# hbridge.net
KiCad netlist of a schematic drawn in EAGLE
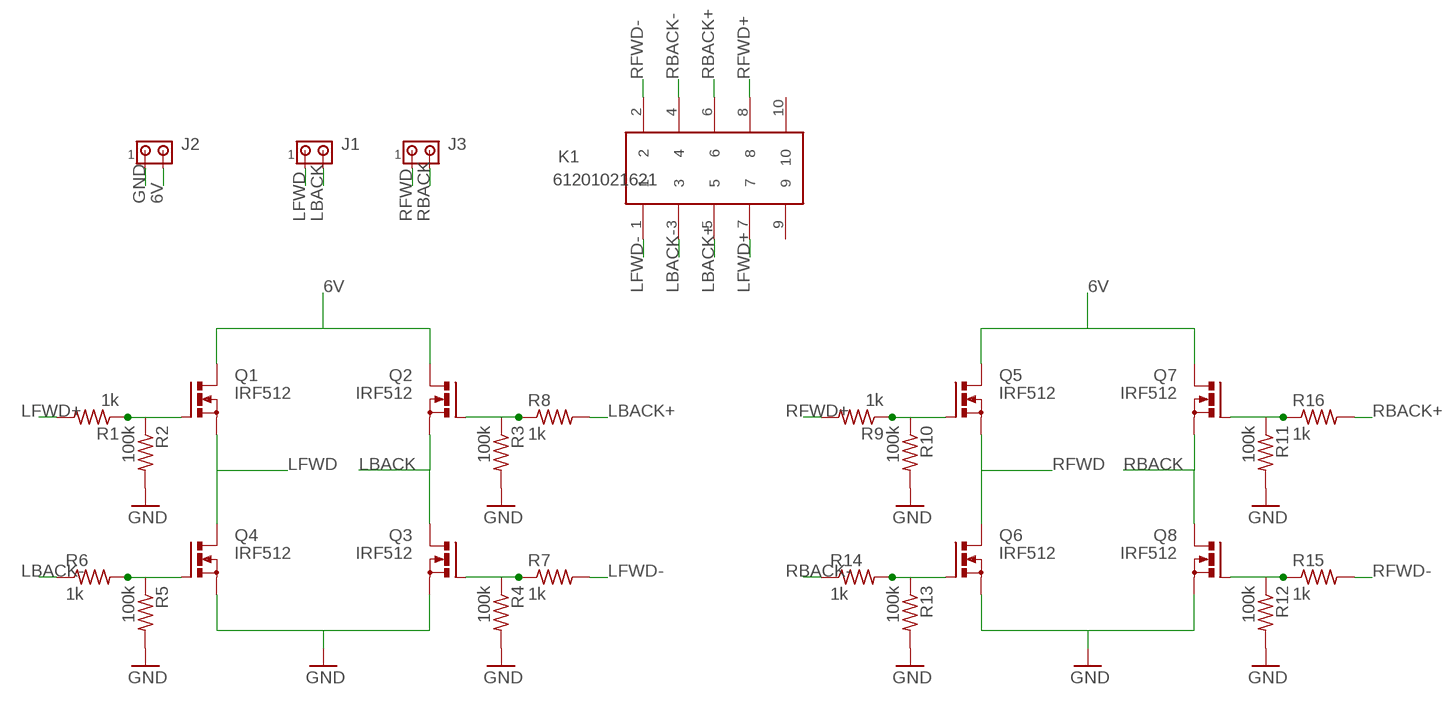
[diagram p0: schematic, sheet 1]

(export (version "E")
  (design (tool "Eeschema 10.0.6"))
  (components
    (comp (ref "J1")
      (value "MTA02-100")
      (footprint "eagle-import:10X02MTA")
      (libsource (lib "eagle-import") (part "MTA02-100"))
    )
    (comp (ref "J2")
      (value "MTA02-100")
      (footprint "eagle-import:10X02MTA")
      (libsource (lib "eagle-import") (part "MTA02-100"))
    )
    (comp (ref "J3")
      (value "MTA02-100")
      (footprint "eagle-import:10X02MTA")
      (libsource (lib "eagle-import") (part "MTA02-100"))
    )
    (comp (ref "K1")
      (value "61201021621")
      (footprint "eagle-import:61201021621")
      (libsource (lib "eagle-import") (part "61201021621"))
    )
    (comp (ref "Q1")
      (value "IRF512")
      (footprint "eagle-import:TO220BV")
      (libsource (lib "eagle-import") (part "IRF512"))
    )
    (comp (ref "Q2")
      (value "IRF512")
      (footprint "eagle-import:TO220BV")
      (libsource (lib "eagle-import") (part "IRF512"))
    )
    (comp (ref "Q3")
      (value "IRF512")
      (footprint "eagle-import:TO220BV")
      (libsource (lib "eagle-import") (part "IRF512"))
    )
    (comp (ref "Q4")
      (value "IRF512")
      (footprint "eagle-import:TO220BV")
      (libsource (lib "eagle-import") (part "IRF512"))
    )
    (comp (ref "Q5")
      (value "IRF512")
      (footprint "eagle-import:TO220BV")
      (libsource (lib "eagle-import") (part "IRF512"))
    )
    (comp (ref "Q6")
      (value "IRF512")
      (footprint "eagle-import:TO220BV")
      (libsource (lib "eagle-import") (part "IRF512"))
    )
    (comp (ref "Q7")
      (value "IRF512")
      (footprint "eagle-import:TO220BV")
      (libsource (lib "eagle-import") (part "IRF512"))
    )
    (comp (ref "Q8")
      (value "IRF512")
      (footprint "eagle-import:TO220BV")
      (libsource (lib "eagle-import") (part "IRF512"))
    )
    (comp (ref "R1")
      (value "1k")
      (footprint "eagle-import:0204_7")
      (libsource (lib "eagle-import") (part "R-US_0204/7"))
    )
    (comp (ref "R2")
      (value "100k")
      (footprint "eagle-import:0204_7")
      (libsource (lib "eagle-import") (part "R-US_0204/7"))
    )
    (comp (ref "R3")
      (value "100k")
      (footprint "eagle-import:0204_7")
      (libsource (lib "eagle-import") (part "R-US_0204/7"))
    )
    (comp (ref "R4")
      (value "100k")
      (footprint "eagle-import:0204_7")
      (libsource (lib "eagle-import") (part "R-US_0204/7"))
    )
    (comp (ref "R5")
      (value "100k")
      (footprint "eagle-import:0204_7")
      (libsource (lib "eagle-import") (part "R-US_0204/7"))
    )
    (comp (ref "R6")
      (value "1k")
      (footprint "eagle-import:0204_7")
      (libsource (lib "eagle-import") (part "R-US_0204/7"))
    )
    (comp (ref "R7")
      (value "1k")
      (footprint "eagle-import:0204_7")
      (libsource (lib "eagle-import") (part "R-US_0204/7"))
    )
    (comp (ref "R8")
      (value "1k")
      (footprint "eagle-import:0204_7")
      (libsource (lib "eagle-import") (part "R-US_0204/7"))
    )
    (comp (ref "R9")
      (value "1k")
      (footprint "eagle-import:0204_7")
      (libsource (lib "eagle-import") (part "R-US_0204/7"))
    )
    (comp (ref "R10")
      (value "100k")
      (footprint "eagle-import:0204_7")
      (libsource (lib "eagle-import") (part "R-US_0204/7"))
    )
    (comp (ref "R11")
      (value "100k")
      (footprint "eagle-import:0204_7")
      (libsource (lib "eagle-import") (part "R-US_0204/7"))
    )
    (comp (ref "R12")
      (value "100k")
      (footprint "eagle-import:0204_7")
      (libsource (lib "eagle-import") (part "R-US_0204/7"))
    )
    (comp (ref "R13")
      (value "100k")
      (footprint "eagle-import:0204_7")
      (libsource (lib "eagle-import") (part "R-US_0204/7"))
    )
    (comp (ref "R14")
      (value "1k")
      (footprint "eagle-import:0204_7")
      (libsource (lib "eagle-import") (part "R-US_0204/7"))
    )
    (comp (ref "R15")
      (value "1k")
      (footprint "eagle-import:0204_7")
      (libsource (lib "eagle-import") (part "R-US_0204/7"))
    )
    (comp (ref "R16")
      (value "1k")
      (footprint "eagle-import:0204_7")
      (libsource (lib "eagle-import") (part "R-US_0204/7"))
    )
  )
  (nets
    (net (code "1") (name "/6V") (class "Default")
      (node (ref "J2") (pin "2") (pinfunction "2_2") (pintype "passive"))
      (node (ref "Q1") (pin "D") (pinfunction "D_D") (pintype "passive"))
      (node (ref "Q2") (pin "D") (pinfunction "D_D") (pintype "passive"))
      (node (ref "Q5") (pin "D") (pinfunction "D_D") (pintype "passive"))
      (node (ref "Q7") (pin "D") (pinfunction "D_D") (pintype "passive"))
    )
    (net (code "2") (name "/LBACK") (class "Default")
      (node (ref "J1") (pin "2") (pinfunction "2_2") (pintype "passive"))
      (node (ref "Q2") (pin "S") (pinfunction "S_S") (pintype "passive"))
      (node (ref "Q3") (pin "D") (pinfunction "D_D") (pintype "passive"))
    )
    (net (code "3") (name "/LBACK+") (class "Default")
      (node (ref "K1") (pin "5") (pinfunction "5_5") (pintype "passive"))
      (node (ref "R8") (pin "2") (pinfunction "2_2") (pintype "passive"))
    )
    (net (code "4") (name "/LBACK-") (class "Default")
      (node (ref "K1") (pin "3") (pinfunction "3_3") (pintype "passive"))
      (node (ref "R6") (pin "1") (pinfunction "1_1") (pintype "passive"))
    )
    (net (code "5") (name "/LFWD") (class "Default")
      (node (ref "J1") (pin "1") (pinfunction "1_1") (pintype "passive"))
      (node (ref "Q1") (pin "S") (pinfunction "S_S") (pintype "passive"))
      (node (ref "Q4") (pin "D") (pinfunction "D_D") (pintype "passive"))
    )
    (net (code "6") (name "/LFWD+") (class "Default")
      (node (ref "K1") (pin "7") (pinfunction "7_7") (pintype "passive"))
      (node (ref "R1") (pin "2") (pinfunction "2_2") (pintype "passive"))
    )
    (net (code "7") (name "/LFWD-") (class "Default")
      (node (ref "K1") (pin "1") (pinfunction "1_1") (pintype "passive"))
      (node (ref "R7") (pin "2") (pinfunction "2_2") (pintype "passive"))
    )
    (net (code "8") (name "/RBACK") (class "Default")
      (node (ref "J3") (pin "2") (pinfunction "2_2") (pintype "passive"))
      (node (ref "Q7") (pin "S") (pinfunction "S_S") (pintype "passive"))
      (node (ref "Q8") (pin "D") (pinfunction "D_D") (pintype "passive"))
    )
    (net (code "9") (name "/RBACK+") (class "Default")
      (node (ref "K1") (pin "6") (pinfunction "6_6") (pintype "passive"))
      (node (ref "R16") (pin "2") (pinfunction "2_2") (pintype "passive"))
    )
    (net (code "10") (name "/RBACK-") (class "Default")
      (node (ref "K1") (pin "4") (pinfunction "4_4") (pintype "passive"))
      (node (ref "R14") (pin "1") (pinfunction "1_1") (pintype "passive"))
    )
    (net (code "11") (name "/RFWD") (class "Default")
      (node (ref "J3") (pin "1") (pinfunction "1_1") (pintype "passive"))
      (node (ref "Q5") (pin "S") (pinfunction "S_S") (pintype "passive"))
      (node (ref "Q6") (pin "D") (pinfunction "D_D") (pintype "passive"))
    )
    (net (code "12") (name "/RFWD+") (class "Default")
      (node (ref "K1") (pin "8") (pinfunction "8_8") (pintype "passive"))
      (node (ref "R9") (pin "2") (pinfunction "2_2") (pintype "passive"))
    )
    (net (code "13") (name "/RFWD-") (class "Default")
      (node (ref "K1") (pin "2") (pinfunction "2_2") (pintype "passive"))
      (node (ref "R15") (pin "2") (pinfunction "2_2") (pintype "passive"))
    )
    (net (code "14") (name "GND") (class "Default")
      (node (ref "J2") (pin "1") (pinfunction "1_1") (pintype "passive"))
      (node (ref "Q3") (pin "S") (pinfunction "S_S") (pintype "passive"))
      (node (ref "Q4") (pin "S") (pinfunction "S_S") (pintype "passive"))
      (node (ref "Q6") (pin "S") (pinfunction "S_S") (pintype "passive"))
      (node (ref "Q8") (pin "S") (pinfunction "S_S") (pintype "passive"))
      (node (ref "R10") (pin "2") (pinfunction "2_2") (pintype "passive"))
      (node (ref "R11") (pin "2") (pinfunction "2_2") (pintype "passive"))
      (node (ref "R12") (pin "2") (pinfunction "2_2") (pintype "passive"))
      (node (ref "R13") (pin "2") (pinfunction "2_2") (pintype "passive"))
      (node (ref "R2") (pin "2") (pinfunction "2_2") (pintype "passive"))
      (node (ref "R3") (pin "2") (pinfunction "2_2") (pintype "passive"))
      (node (ref "R4") (pin "2") (pinfunction "2_2") (pintype "passive"))
      (node (ref "R5") (pin "2") (pinfunction "2_2") (pintype "passive"))
    )
    (net (code "15") (name "Net-(Q1-PadG)") (class "Default")
      (node (ref "Q1") (pin "G") (pinfunction "G_G") (pintype "passive"))
      (node (ref "R1") (pin "1") (pinfunction "1_1") (pintype "passive"))
      (node (ref "R2") (pin "1") (pinfunction "1_1") (pintype "passive"))
    )
    (net (code "16") (name "Net-(Q2-PadG)") (class "Default")
      (node (ref "Q2") (pin "G") (pinfunction "G_G") (pintype "passive"))
      (node (ref "R3") (pin "1") (pinfunction "1_1") (pintype "passive"))
      (node (ref "R8") (pin "1") (pinfunction "1_1") (pintype "passive"))
    )
    (net (code "17") (name "Net-(Q3-PadG)") (class "Default")
      (node (ref "Q3") (pin "G") (pinfunction "G_G") (pintype "passive"))
      (node (ref "R4") (pin "1") (pinfunction "1_1") (pintype "passive"))
      (node (ref "R7") (pin "1") (pinfunction "1_1") (pintype "passive"))
    )
    (net (code "18") (name "Net-(Q4-PadG)") (class "Default")
      (node (ref "Q4") (pin "G") (pinfunction "G_G") (pintype "passive"))
      (node (ref "R5") (pin "1") (pinfunction "1_1") (pintype "passive"))
      (node (ref "R6") (pin "2") (pinfunction "2_2") (pintype "passive"))
    )
    (net (code "19") (name "Net-(Q5-PadG)") (class "Default")
      (node (ref "Q5") (pin "G") (pinfunction "G_G") (pintype "passive"))
      (node (ref "R10") (pin "1") (pinfunction "1_1") (pintype "passive"))
      (node (ref "R9") (pin "1") (pinfunction "1_1") (pintype "passive"))
    )
    (net (code "20") (name "Net-(Q6-PadG)") (class "Default")
      (node (ref "Q6") (pin "G") (pinfunction "G_G") (pintype "passive"))
      (node (ref "R13") (pin "1") (pinfunction "1_1") (pintype "passive"))
      (node (ref "R14") (pin "2") (pinfunction "2_2") (pintype "passive"))
    )
    (net (code "21") (name "Net-(Q7-PadG)") (class "Default")
      (node (ref "Q7") (pin "G") (pinfunction "G_G") (pintype "passive"))
      (node (ref "R11") (pin "1") (pinfunction "1_1") (pintype "passive"))
      (node (ref "R16") (pin "1") (pinfunction "1_1") (pintype "passive"))
    )
    (net (code "22") (name "Net-(Q8-PadG)") (class "Default")
      (node (ref "Q8") (pin "G") (pinfunction "G_G") (pintype "passive"))
      (node (ref "R12") (pin "1") (pinfunction "1_1") (pintype "passive"))
      (node (ref "R15") (pin "1") (pinfunction "1_1") (pintype "passive"))
    )
    (net (code "23") (name "unconnected-(K1-Pad9)") (class "Default")
      (node (ref "K1") (pin "9") (pinfunction "9_9") (pintype "passive"))
    )
    (net (code "24") (name "unconnected-(K1-Pad10)") (class "Default")
      (node (ref "K1") (pin "10") (pinfunction "10_10") (pintype "passive"))
    )
  )
)
